# HEADER_1.net
KiCad netlist of a schematic drawn in Altium Designer
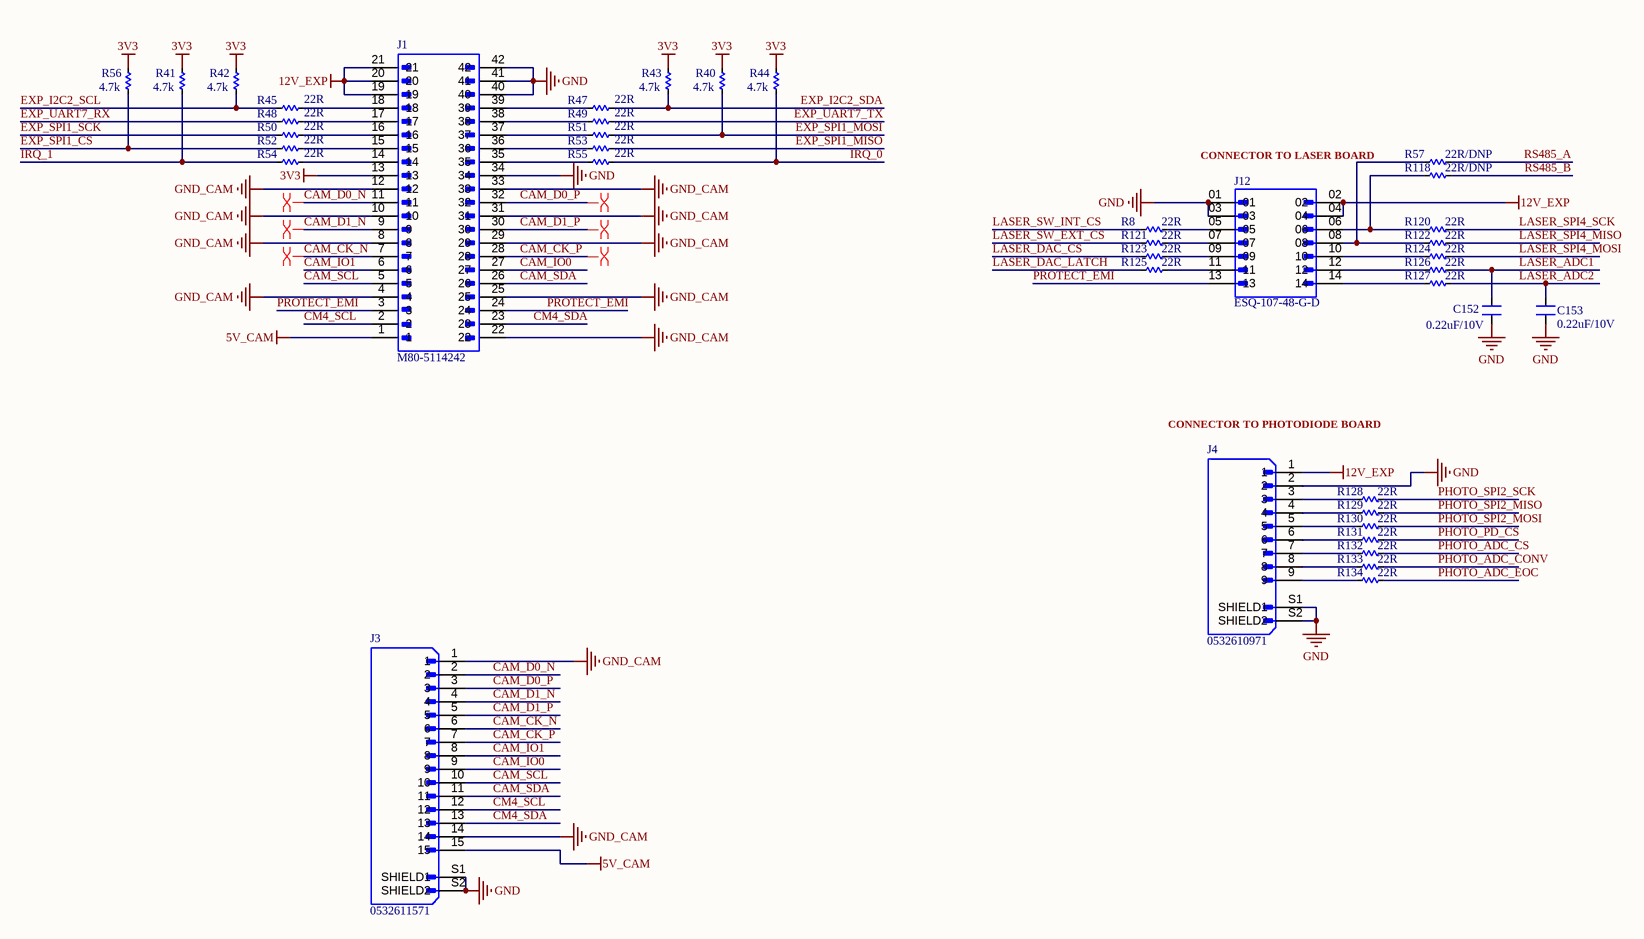
[diagram p0: HEADER_1.SchDoc]

(export (version "E")
  (design (tool "Eeschema 10.0.6"))
  (components
    (comp (ref "C152")
      (value "0.22uF/10V")
      (footprint "CAP_C_1608X80")
      (libsource (lib "EXP_HW_V3") (part "Capacitors"))
    )
    (comp (ref "C153")
      (value "0.22uF/10V")
      (footprint "CAP_C_1608X80")
      (libsource (lib "EXP_HW_V3") (part "Capacitors"))
    )
    (comp (ref "J1")
      (value "M80-5114242")
      (footprint "M80-5114242")
      (description "CONN HEADER VERT 42POS 2MM")
      (libsource (lib "EXP_HW_V2") (part "CONN_TH_42"))
    )
    (comp (ref "J3")
      (value "0532611571")
      (footprint "0532611571")
      (description "Conn Shrouded Header (4 Sides) HDR 15 POS 1.25mm Solder RA Side Entry SMD PicoBladeâ„¢ T/R")
      (fields (field (name "MP") "532611571") (field (name "MF") "Molex"))
      (libsource (lib "EXP_HW_V2") (part "CONN_SMD_15"))
    )
    (comp (ref "J4")
      (value "0532610971")
      (footprint "0532610971")
      (description "CONN HEADER SMD R/A 9POS 1.25MM")
      (libsource (lib "EXP_HW_V3") (part "CONN_SMD_09"))
    )
    (comp (ref "J12")
      (value "ESQ-107-48-G-D")
      (footprint "ESQ-107-37-G-D")
      (description "CONN SOCKET 14POS 0.1 GOLD PCB")
      (libsource (lib "EXP_HW_V2") (part "CONN_TH_14"))
    )
    (comp (ref "R8")
      (value "22R")
      (footprint "RES_C_1608X60")
      (description "SMD")
      (fields
        (field (name "MANUFACTURER") "Generic Components")
        (field (name "PUBLISHER") "Altium Hobart Technology Centre")
      )
      (libsource (lib "EXP_HW_V3") (part "Res SMD"))
    )
    (comp (ref "R40")
      (value "4.7k")
      (footprint "RES_C_1608X60")
      (description "SMD")
      (fields
        (field (name "MANUFACTURER") "Generic Components")
        (field (name "PUBLISHER") "Altium Hobart Technology Centre")
      )
      (libsource (lib "EXP_HW_V3") (part "Res SMD"))
    )
    (comp (ref "R41")
      (value "4.7k")
      (footprint "RES_C_1608X60")
      (description "SMD")
      (fields
        (field (name "MANUFACTURER") "Generic Components")
        (field (name "PUBLISHER") "Altium Hobart Technology Centre")
      )
      (libsource (lib "EXP_HW_V3") (part "Res SMD"))
    )
    (comp (ref "R42")
      (value "4.7k")
      (footprint "RES_C_1608X60")
      (description "SMD")
      (fields
        (field (name "MANUFACTURER") "Generic Components")
        (field (name "PUBLISHER") "Altium Hobart Technology Centre")
      )
      (libsource (lib "EXP_HW_V3") (part "Res SMD"))
    )
    (comp (ref "R43")
      (value "4.7k")
      (footprint "RES_C_1608X60")
      (description "SMD")
      (fields
        (field (name "MANUFACTURER") "Generic Components")
        (field (name "PUBLISHER") "Altium Hobart Technology Centre")
      )
      (libsource (lib "EXP_HW_V3") (part "Res SMD"))
    )
    (comp (ref "R44")
      (value "4.7k")
      (footprint "RES_C_1608X60")
      (description "SMD")
      (fields
        (field (name "MANUFACTURER") "Generic Components")
        (field (name "PUBLISHER") "Altium Hobart Technology Centre")
      )
      (libsource (lib "EXP_HW_V3") (part "Res SMD"))
    )
    (comp (ref "R45")
      (value "22R")
      (footprint "RES_C_1608X60")
      (description "SMD")
      (fields
        (field (name "MANUFACTURER") "Generic Components")
        (field (name "PUBLISHER") "Altium Hobart Technology Centre")
      )
      (libsource (lib "EXP_HW_V3") (part "Res SMD"))
    )
    (comp (ref "R47")
      (value "22R")
      (footprint "RES_C_1608X60")
      (description "SMD")
      (fields
        (field (name "MANUFACTURER") "Generic Components")
        (field (name "PUBLISHER") "Altium Hobart Technology Centre")
      )
      (libsource (lib "EXP_HW_V3") (part "Res SMD"))
    )
    (comp (ref "R48")
      (value "22R")
      (footprint "RES_C_1608X60")
      (description "SMD")
      (fields
        (field (name "MANUFACTURER") "Generic Components")
        (field (name "PUBLISHER") "Altium Hobart Technology Centre")
      )
      (libsource (lib "EXP_HW_V3") (part "Res SMD"))
    )
    (comp (ref "R49")
      (value "22R")
      (footprint "RES_C_1608X60")
      (description "SMD")
      (fields
        (field (name "MANUFACTURER") "Generic Components")
        (field (name "PUBLISHER") "Altium Hobart Technology Centre")
      )
      (libsource (lib "EXP_HW_V3") (part "Res SMD"))
    )
    (comp (ref "R50")
      (value "22R")
      (footprint "RES_C_1608X60")
      (description "SMD")
      (fields
        (field (name "MANUFACTURER") "Generic Components")
        (field (name "PUBLISHER") "Altium Hobart Technology Centre")
      )
      (libsource (lib "EXP_HW_V3") (part "Res SMD"))
    )
    (comp (ref "R51")
      (value "22R")
      (footprint "RES_C_1608X60")
      (description "SMD")
      (fields
        (field (name "MANUFACTURER") "Generic Components")
        (field (name "PUBLISHER") "Altium Hobart Technology Centre")
      )
      (libsource (lib "EXP_HW_V3") (part "Res SMD"))
    )
    (comp (ref "R52")
      (value "22R")
      (footprint "RES_C_1608X60")
      (description "SMD")
      (fields
        (field (name "MANUFACTURER") "Generic Components")
        (field (name "PUBLISHER") "Altium Hobart Technology Centre")
      )
      (libsource (lib "EXP_HW_V3") (part "Res SMD"))
    )
    (comp (ref "R53")
      (value "22R")
      (footprint "RES_C_1608X60")
      (description "SMD")
      (fields
        (field (name "MANUFACTURER") "Generic Components")
        (field (name "PUBLISHER") "Altium Hobart Technology Centre")
      )
      (libsource (lib "EXP_HW_V3") (part "Res SMD"))
    )
    (comp (ref "R54")
      (value "22R")
      (footprint "RES_C_1608X60")
      (description "SMD")
      (fields
        (field (name "MANUFACTURER") "Generic Components")
        (field (name "PUBLISHER") "Altium Hobart Technology Centre")
      )
      (libsource (lib "EXP_HW_V3") (part "Res SMD"))
    )
    (comp (ref "R55")
      (value "22R")
      (footprint "RES_C_1608X60")
      (description "SMD")
      (fields
        (field (name "MANUFACTURER") "Generic Components")
        (field (name "PUBLISHER") "Altium Hobart Technology Centre")
      )
      (libsource (lib "EXP_HW_V3") (part "Res SMD"))
    )
    (comp (ref "R56")
      (value "4.7k")
      (footprint "RES_C_1608X60")
      (description "SMD")
      (fields
        (field (name "MANUFACTURER") "Generic Components")
        (field (name "PUBLISHER") "Altium Hobart Technology Centre")
      )
      (libsource (lib "EXP_HW_V3") (part "Res SMD"))
    )
    (comp (ref "R57")
      (value "22R/DNP")
      (footprint "RES_C_1608X60")
      (description "SMD")
      (fields
        (field (name "MANUFACTURER") "Generic Components")
        (field (name "PUBLISHER") "Altium Hobart Technology Centre")
      )
      (libsource (lib "EXP_HW_V3") (part "Res SMD"))
    )
    (comp (ref "R118")
      (value "22R/DNP")
      (footprint "RES_C_1608X60")
      (description "SMD")
      (fields
        (field (name "MANUFACTURER") "Generic Components")
        (field (name "PUBLISHER") "Altium Hobart Technology Centre")
      )
      (libsource (lib "EXP_HW_V3") (part "Res SMD"))
    )
    (comp (ref "R120")
      (value "22R")
      (footprint "RES_C_1608X60")
      (description "SMD")
      (fields
        (field (name "MANUFACTURER") "Generic Components")
        (field (name "PUBLISHER") "Altium Hobart Technology Centre")
      )
      (libsource (lib "EXP_HW_V3") (part "Res SMD"))
    )
    (comp (ref "R121")
      (value "22R")
      (footprint "RES_C_1608X60")
      (description "SMD")
      (fields
        (field (name "MANUFACTURER") "Generic Components")
        (field (name "PUBLISHER") "Altium Hobart Technology Centre")
      )
      (libsource (lib "EXP_HW_V3") (part "Res SMD"))
    )
    (comp (ref "R122")
      (value "22R")
      (footprint "RES_C_1608X60")
      (description "SMD")
      (fields
        (field (name "MANUFACTURER") "Generic Components")
        (field (name "PUBLISHER") "Altium Hobart Technology Centre")
      )
      (libsource (lib "EXP_HW_V3") (part "Res SMD"))
    )
    (comp (ref "R123")
      (value "22R")
      (footprint "RES_C_1608X60")
      (description "SMD")
      (fields
        (field (name "MANUFACTURER") "Generic Components")
        (field (name "PUBLISHER") "Altium Hobart Technology Centre")
      )
      (libsource (lib "EXP_HW_V3") (part "Res SMD"))
    )
    (comp (ref "R124")
      (value "22R")
      (footprint "RES_C_1608X60")
      (description "SMD")
      (fields
        (field (name "MANUFACTURER") "Generic Components")
        (field (name "PUBLISHER") "Altium Hobart Technology Centre")
      )
      (libsource (lib "EXP_HW_V3") (part "Res SMD"))
    )
    (comp (ref "R125")
      (value "22R")
      (footprint "RES_C_1608X60")
      (description "SMD")
      (fields
        (field (name "MANUFACTURER") "Generic Components")
        (field (name "PUBLISHER") "Altium Hobart Technology Centre")
      )
      (libsource (lib "EXP_HW_V3") (part "Res SMD"))
    )
    (comp (ref "R126")
      (value "22R")
      (footprint "RES_C_1608X60")
      (description "SMD")
      (fields
        (field (name "MANUFACTURER") "Generic Components")
        (field (name "PUBLISHER") "Altium Hobart Technology Centre")
      )
      (libsource (lib "EXP_HW_V3") (part "Res SMD"))
    )
    (comp (ref "R127")
      (value "22R")
      (footprint "RES_C_1608X60")
      (description "SMD")
      (fields
        (field (name "MANUFACTURER") "Generic Components")
        (field (name "PUBLISHER") "Altium Hobart Technology Centre")
      )
      (libsource (lib "EXP_HW_V3") (part "Res SMD"))
    )
    (comp (ref "R128")
      (value "22R")
      (footprint "RES_C_1608X60")
      (description "SMD")
      (fields
        (field (name "MANUFACTURER") "Generic Components")
        (field (name "PUBLISHER") "Altium Hobart Technology Centre")
      )
      (libsource (lib "EXP_HW_V3") (part "Res SMD"))
    )
    (comp (ref "R129")
      (value "22R")
      (footprint "RES_C_1608X60")
      (description "SMD")
      (fields
        (field (name "MANUFACTURER") "Generic Components")
        (field (name "PUBLISHER") "Altium Hobart Technology Centre")
      )
      (libsource (lib "EXP_HW_V3") (part "Res SMD"))
    )
    (comp (ref "R130")
      (value "22R")
      (footprint "RES_C_1608X60")
      (description "SMD")
      (fields
        (field (name "MANUFACTURER") "Generic Components")
        (field (name "PUBLISHER") "Altium Hobart Technology Centre")
      )
      (libsource (lib "EXP_HW_V3") (part "Res SMD"))
    )
    (comp (ref "R131")
      (value "22R")
      (footprint "RES_C_1608X60")
      (description "SMD")
      (fields
        (field (name "MANUFACTURER") "Generic Components")
        (field (name "PUBLISHER") "Altium Hobart Technology Centre")
      )
      (libsource (lib "EXP_HW_V3") (part "Res SMD"))
    )
    (comp (ref "R132")
      (value "22R")
      (footprint "RES_C_1608X60")
      (description "SMD")
      (fields
        (field (name "MANUFACTURER") "Generic Components")
        (field (name "PUBLISHER") "Altium Hobart Technology Centre")
      )
      (libsource (lib "EXP_HW_V3") (part "Res SMD"))
    )
    (comp (ref "R133")
      (value "22R")
      (footprint "RES_C_1608X60")
      (description "SMD")
      (fields
        (field (name "MANUFACTURER") "Generic Components")
        (field (name "PUBLISHER") "Altium Hobart Technology Centre")
      )
      (libsource (lib "EXP_HW_V3") (part "Res SMD"))
    )
    (comp (ref "R134")
      (value "22R")
      (footprint "RES_C_1608X60")
      (description "SMD")
      (fields
        (field (name "MANUFACTURER") "Generic Components")
        (field (name "PUBLISHER") "Altium Hobart Technology Centre")
      )
      (libsource (lib "EXP_HW_V3") (part "Res SMD"))
    )
  )
  (nets
    (net (code "1") (name "/CAM_CK_N") (class "Default")
      (node (ref "J1") (pin "7") (pinfunction "7_7") (pintype "passive"))
      (node (ref "J3") (pin "6") (pinfunction "6_6") (pintype "passive"))
    )
    (net (code "2") (name "/CAM_CK_P") (class "Default")
      (node (ref "J1") (pin "28") (pinfunction "28_28") (pintype "passive"))
      (node (ref "J3") (pin "7") (pinfunction "7_7") (pintype "passive"))
    )
    (net (code "3") (name "/CAM_D0_N") (class "Default")
      (node (ref "J1") (pin "11") (pinfunction "11_11") (pintype "passive"))
      (node (ref "J3") (pin "2") (pinfunction "2_2") (pintype "passive"))
    )
    (net (code "4") (name "/CAM_D0_P") (class "Default")
      (node (ref "J1") (pin "32") (pinfunction "32_32") (pintype "passive"))
      (node (ref "J3") (pin "3") (pinfunction "3_3") (pintype "passive"))
    )
    (net (code "5") (name "/CAM_D1_N") (class "Default")
      (node (ref "J1") (pin "9") (pinfunction "9_9") (pintype "passive"))
      (node (ref "J3") (pin "4") (pinfunction "4_4") (pintype "passive"))
    )
    (net (code "6") (name "/CAM_D1_P") (class "Default")
      (node (ref "J1") (pin "30") (pinfunction "30_30") (pintype "passive"))
      (node (ref "J3") (pin "5") (pinfunction "5_5") (pintype "passive"))
    )
    (net (code "7") (name "/CAM_IO0") (class "Default")
      (node (ref "J1") (pin "27") (pinfunction "27_27") (pintype "passive"))
      (node (ref "J3") (pin "9") (pinfunction "9_9") (pintype "passive"))
    )
    (net (code "8") (name "/CAM_IO1") (class "Default")
      (node (ref "J1") (pin "6") (pinfunction "6_6") (pintype "passive"))
      (node (ref "J3") (pin "8") (pinfunction "8_8") (pintype "passive"))
    )
    (net (code "9") (name "/CAM_SCL") (class "Default")
      (node (ref "J1") (pin "5") (pinfunction "5_5") (pintype "passive"))
      (node (ref "J3") (pin "10") (pinfunction "10_10") (pintype "passive"))
    )
    (net (code "10") (name "/CAM_SDA") (class "Default")
      (node (ref "J1") (pin "26") (pinfunction "26_26") (pintype "passive"))
      (node (ref "J3") (pin "11") (pinfunction "11_11") (pintype "passive"))
    )
    (net (code "11") (name "/CM4_SCL") (class "Default")
      (node (ref "J1") (pin "2") (pinfunction "2_2") (pintype "passive"))
      (node (ref "J3") (pin "12") (pinfunction "12_12") (pintype "passive"))
    )
    (net (code "12") (name "/CM4_SDA") (class "Default")
      (node (ref "J1") (pin "23") (pinfunction "23_23") (pintype "passive"))
      (node (ref "J3") (pin "13") (pinfunction "13_13") (pintype "passive"))
    )
    (net (code "13") (name "/EXP_I2C2_SCL") (class "Default")
      (node (ref "R42") (pin "2") (pinfunction "2_2") (pintype "passive"))
      (node (ref "R45") (pin "1") (pinfunction "1_1") (pintype "passive"))
    )
    (net (code "14") (name "/EXP_I2C2_SDA") (class "Default")
      (node (ref "R43") (pin "2") (pinfunction "2_2") (pintype "passive"))
      (node (ref "R47") (pin "2") (pinfunction "2_2") (pintype "passive"))
    )
    (net (code "15") (name "/EXP_SPI1_CS") (class "Default")
      (node (ref "R52") (pin "1") (pinfunction "1_1") (pintype "passive"))
      (node (ref "R56") (pin "2") (pinfunction "2_2") (pintype "passive"))
    )
    (net (code "16") (name "/EXP_SPI1_MISO") (class "Default")
      (node (ref "R53") (pin "2") (pinfunction "2_2") (pintype "passive"))
    )
    (net (code "17") (name "/EXP_SPI1_MOSI") (class "Default")
      (node (ref "R40") (pin "2") (pinfunction "2_2") (pintype "passive"))
      (node (ref "R51") (pin "2") (pinfunction "2_2") (pintype "passive"))
    )
    (net (code "18") (name "/EXP_SPI1_SCK") (class "Default")
      (node (ref "R50") (pin "1") (pinfunction "1_1") (pintype "passive"))
    )
    (net (code "19") (name "/EXP_UART7_RX") (class "Default")
      (node (ref "R48") (pin "1") (pinfunction "1_1") (pintype "passive"))
    )
    (net (code "20") (name "/EXP_UART7_TX") (class "Default")
      (node (ref "R49") (pin "2") (pinfunction "2_2") (pintype "passive"))
    )
    (net (code "21") (name "/IRQ_0") (class "Default")
      (node (ref "R44") (pin "2") (pinfunction "2_2") (pintype "passive"))
      (node (ref "R55") (pin "2") (pinfunction "2_2") (pintype "passive"))
    )
    (net (code "22") (name "/IRQ_1") (class "Default")
      (node (ref "R41") (pin "2") (pinfunction "2_2") (pintype "passive"))
      (node (ref "R54") (pin "1") (pinfunction "1_1") (pintype "passive"))
    )
    (net (code "23") (name "/LASER_ADC1") (class "Default")
      (node (ref "C152") (pin "2") (pinfunction "2_2") (pintype "passive"))
      (node (ref "R126") (pin "2") (pinfunction "2_2") (pintype "passive"))
    )
    (net (code "24") (name "/LASER_ADC2") (class "Default")
      (node (ref "C153") (pin "2") (pinfunction "2_2") (pintype "passive"))
      (node (ref "R127") (pin "2") (pinfunction "2_2") (pintype "passive"))
    )
    (net (code "25") (name "/LASER_DAC_CS") (class "Default")
      (node (ref "R123") (pin "1") (pinfunction "1_1") (pintype "passive"))
    )
    (net (code "26") (name "/LASER_DAC_LATCH") (class "Default")
      (node (ref "R125") (pin "1") (pinfunction "1_1") (pintype "passive"))
    )
    (net (code "27") (name "/LASER_SPI4_MISO") (class "Default")
      (node (ref "R122") (pin "2") (pinfunction "2_2") (pintype "passive"))
    )
    (net (code "28") (name "/LASER_SPI4_MOSI") (class "Default")
      (node (ref "R124") (pin "2") (pinfunction "2_2") (pintype "passive"))
    )
    (net (code "29") (name "/LASER_SPI4_SCK") (class "Default")
      (node (ref "R120") (pin "2") (pinfunction "2_2") (pintype "passive"))
    )
    (net (code "30") (name "/LASER_SW_EXT_CS") (class "Default")
      (node (ref "R121") (pin "1") (pinfunction "1_1") (pintype "passive"))
    )
    (net (code "31") (name "/LASER_SW_INT_CS") (class "Default")
      (node (ref "R8") (pin "1") (pinfunction "1_1") (pintype "passive"))
    )
    (net (code "32") (name "/PHOTO_ADC_CONV") (class "Default")
      (node (ref "R133") (pin "2") (pinfunction "2_2") (pintype "passive"))
    )
    (net (code "33") (name "/PHOTO_ADC_CS") (class "Default")
      (node (ref "R132") (pin "2") (pinfunction "2_2") (pintype "passive"))
    )
    (net (code "34") (name "/PHOTO_ADC_EOC") (class "Default")
      (node (ref "R134") (pin "2") (pinfunction "2_2") (pintype "passive"))
    )
    (net (code "35") (name "/PHOTO_PD_CS") (class "Default")
      (node (ref "R131") (pin "2") (pinfunction "2_2") (pintype "passive"))
    )
    (net (code "36") (name "/PHOTO_SPI2_MISO") (class "Default")
      (node (ref "R129") (pin "2") (pinfunction "2_2") (pintype "passive"))
    )
    (net (code "37") (name "/PHOTO_SPI2_MOSI") (class "Default")
      (node (ref "R130") (pin "2") (pinfunction "2_2") (pintype "passive"))
    )
    (net (code "38") (name "/PHOTO_SPI2_SCK") (class "Default")
      (node (ref "R128") (pin "2") (pinfunction "2_2") (pintype "passive"))
    )
    (net (code "39") (name "/PROTECT_EMI") (class "Default")
      (node (ref "J1") (pin "24") (pinfunction "24_24") (pintype "passive"))
      (node (ref "J1") (pin "3") (pinfunction "3_3") (pintype "passive"))
      (node (ref "J12") (pin "13") (pinfunction "13_13") (pintype "passive"))
    )
    (net (code "40") (name "/RS485_A") (class "Default")
      (node (ref "R57") (pin "2") (pinfunction "2_2") (pintype "passive"))
    )
    (net (code "41") (name "/RS485_B") (class "Default")
      (node (ref "R118") (pin "2") (pinfunction "2_2") (pintype "passive"))
    )
    (net (code "42") (name "3V3") (class "Default")
      (node (ref "J1") (pin "13") (pinfunction "13_13") (pintype "passive"))
      (node (ref "R40") (pin "1") (pinfunction "1_1") (pintype "passive"))
      (node (ref "R41") (pin "1") (pinfunction "1_1") (pintype "passive"))
      (node (ref "R42") (pin "1") (pinfunction "1_1") (pintype "passive"))
      (node (ref "R43") (pin "1") (pinfunction "1_1") (pintype "passive"))
      (node (ref "R44") (pin "1") (pinfunction "1_1") (pintype "passive"))
      (node (ref "R56") (pin "1") (pinfunction "1_1") (pintype "passive"))
    )
    (net (code "43") (name "5V_CAM") (class "Default")
      (node (ref "J1") (pin "1") (pinfunction "1_1") (pintype "passive"))
      (node (ref "J3") (pin "15") (pinfunction "15_15") (pintype "passive"))
    )
    (net (code "44") (name "12V_EXP") (class "Default")
      (node (ref "J1") (pin "19") (pinfunction "19_19") (pintype "passive"))
      (node (ref "J1") (pin "20") (pinfunction "20_20") (pintype "passive"))
      (node (ref "J1") (pin "21") (pinfunction "21_21") (pintype "passive"))
      (node (ref "J12") (pin "02") (pinfunction "02_02") (pintype "passive"))
      (node (ref "J12") (pin "04") (pinfunction "04_04") (pintype "passive"))
      (node (ref "J4") (pin "1") (pinfunction "1_1") (pintype "passive"))
    )
    (net (code "45") (name "GND") (class "Default")
      (node (ref "C152") (pin "1") (pinfunction "1_1") (pintype "passive"))
      (node (ref "C153") (pin "1") (pinfunction "1_1") (pintype "passive"))
      (node (ref "J1") (pin "34") (pinfunction "34_34") (pintype "passive"))
      (node (ref "J1") (pin "40") (pinfunction "40_40") (pintype "passive"))
      (node (ref "J1") (pin "41") (pinfunction "41_41") (pintype "passive"))
      (node (ref "J1") (pin "42") (pinfunction "42_42") (pintype "passive"))
      (node (ref "J12") (pin "01") (pinfunction "01_01") (pintype "passive"))
      (node (ref "J12") (pin "03") (pinfunction "03_03") (pintype "passive"))
      (node (ref "J3") (pin "S1") (pinfunction "SHIELD1_S1") (pintype "passive"))
      (node (ref "J3") (pin "S2") (pinfunction "SHIELD2_S2") (pintype "passive"))
      (node (ref "J4") (pin "2") (pinfunction "2_2") (pintype "passive"))
      (node (ref "J4") (pin "S1") (pinfunction "SHIELD1_S1") (pintype "passive"))
      (node (ref "J4") (pin "S2") (pinfunction "SHIELD2_S2") (pintype "passive"))
    )
    (net (code "46") (name "GND_CAM") (class "Default")
      (node (ref "J1") (pin "10") (pinfunction "10_10") (pintype "passive"))
      (node (ref "J1") (pin "12") (pinfunction "12_12") (pintype "passive"))
      (node (ref "J1") (pin "22") (pinfunction "22_22") (pintype "passive"))
      (node (ref "J1") (pin "25") (pinfunction "25_25") (pintype "passive"))
      (node (ref "J1") (pin "29") (pinfunction "29_29") (pintype "passive"))
      (node (ref "J1") (pin "31") (pinfunction "31_31") (pintype "passive"))
      (node (ref "J1") (pin "33") (pinfunction "33_33") (pintype "passive"))
      (node (ref "J1") (pin "4") (pinfunction "4_4") (pintype "passive"))
      (node (ref "J1") (pin "8") (pinfunction "8_8") (pintype "passive"))
      (node (ref "J3") (pin "1") (pinfunction "1_1") (pintype "passive"))
      (node (ref "J3") (pin "14") (pinfunction "14_14") (pintype "passive"))
    )
    (net (code "47") (name "Net-(J1-Pad14)") (class "Default")
      (node (ref "J1") (pin "14") (pinfunction "14_14") (pintype "passive"))
      (node (ref "R54") (pin "2") (pinfunction "2_2") (pintype "passive"))
    )
    (net (code "48") (name "Net-(J1-Pad15)") (class "Default")
      (node (ref "J1") (pin "15") (pinfunction "15_15") (pintype "passive"))
      (node (ref "R52") (pin "2") (pinfunction "2_2") (pintype "passive"))
    )
    (net (code "49") (name "Net-(J1-Pad16)") (class "Default")
      (node (ref "J1") (pin "16") (pinfunction "16_16") (pintype "passive"))
      (node (ref "R50") (pin "2") (pinfunction "2_2") (pintype "passive"))
    )
    (net (code "50") (name "Net-(J1-Pad17)") (class "Default")
      (node (ref "J1") (pin "17") (pinfunction "17_17") (pintype "passive"))
      (node (ref "R48") (pin "2") (pinfunction "2_2") (pintype "passive"))
    )
    (net (code "51") (name "Net-(J1-Pad18)") (class "Default")
      (node (ref "J1") (pin "18") (pinfunction "18_18") (pintype "passive"))
      (node (ref "R45") (pin "2") (pinfunction "2_2") (pintype "passive"))
    )
    (net (code "52") (name "Net-(J1-Pad35)") (class "Default")
      (node (ref "J1") (pin "35") (pinfunction "35_35") (pintype "passive"))
      (node (ref "R55") (pin "1") (pinfunction "1_1") (pintype "passive"))
    )
    (net (code "53") (name "Net-(J1-Pad36)") (class "Default")
      (node (ref "J1") (pin "36") (pinfunction "36_36") (pintype "passive"))
      (node (ref "R53") (pin "1") (pinfunction "1_1") (pintype "passive"))
    )
    (net (code "54") (name "Net-(J1-Pad37)") (class "Default")
      (node (ref "J1") (pin "37") (pinfunction "37_37") (pintype "passive"))
      (node (ref "R51") (pin "1") (pinfunction "1_1") (pintype "passive"))
    )
    (net (code "55") (name "Net-(J1-Pad38)") (class "Default")
      (node (ref "J1") (pin "38") (pinfunction "38_38") (pintype "passive"))
      (node (ref "R49") (pin "1") (pinfunction "1_1") (pintype "passive"))
    )
    (net (code "56") (name "Net-(J1-Pad39)") (class "Default")
      (node (ref "J1") (pin "39") (pinfunction "39_39") (pintype "passive"))
      (node (ref "R47") (pin "1") (pinfunction "1_1") (pintype "passive"))
    )
    (net (code "57") (name "Net-(J4-Pad3)") (class "Default")
      (node (ref "J4") (pin "3") (pinfunction "3_3") (pintype "passive"))
      (node (ref "R128") (pin "1") (pinfunction "1_1") (pintype "passive"))
    )
    (net (code "58") (name "Net-(J4-Pad4)") (class "Default")
      (node (ref "J4") (pin "4") (pinfunction "4_4") (pintype "passive"))
      (node (ref "R129") (pin "1") (pinfunction "1_1") (pintype "passive"))
    )
    (net (code "59") (name "Net-(J4-Pad5)") (class "Default")
      (node (ref "J4") (pin "5") (pinfunction "5_5") (pintype "passive"))
      (node (ref "R130") (pin "1") (pinfunction "1_1") (pintype "passive"))
    )
    (net (code "60") (name "Net-(J4-Pad6)") (class "Default")
      (node (ref "J4") (pin "6") (pinfunction "6_6") (pintype "passive"))
      (node (ref "R131") (pin "1") (pinfunction "1_1") (pintype "passive"))
    )
    (net (code "61") (name "Net-(J4-Pad7)") (class "Default")
      (node (ref "J4") (pin "7") (pinfunction "7_7") (pintype "passive"))
      (node (ref "R132") (pin "1") (pinfunction "1_1") (pintype "passive"))
    )
    (net (code "62") (name "Net-(J4-Pad8)") (class "Default")
      (node (ref "J4") (pin "8") (pinfunction "8_8") (pintype "passive"))
      (node (ref "R133") (pin "1") (pinfunction "1_1") (pintype "passive"))
    )
    (net (code "63") (name "Net-(J4-Pad9)") (class "Default")
      (node (ref "J4") (pin "9") (pinfunction "9_9") (pintype "passive"))
      (node (ref "R134") (pin "1") (pinfunction "1_1") (pintype "passive"))
    )
    (net (code "64") (name "Net-(J12-Pad05)") (class "Default")
      (node (ref "J12") (pin "05") (pinfunction "05_05") (pintype "passive"))
      (node (ref "R8") (pin "2") (pinfunction "2_2") (pintype "passive"))
    )
    (net (code "65") (name "Net-(J12-Pad06)") (class "Default")
      (node (ref "J12") (pin "06") (pinfunction "06_06") (pintype "passive"))
      (node (ref "R118") (pin "1") (pinfunction "1_1") (pintype "passive"))
      (node (ref "R120") (pin "1") (pinfunction "1_1") (pintype "passive"))
    )
    (net (code "66") (name "Net-(J12-Pad07)") (class "Default")
      (node (ref "J12") (pin "07") (pinfunction "07_07") (pintype "passive"))
      (node (ref "R121") (pin "2") (pinfunction "2_2") (pintype "passive"))
    )
    (net (code "67") (name "Net-(J12-Pad08)") (class "Default")
      (node (ref "J12") (pin "08") (pinfunction "08_08") (pintype "passive"))
      (node (ref "R122") (pin "1") (pinfunction "1_1") (pintype "passive"))
      (node (ref "R57") (pin "1") (pinfunction "1_1") (pintype "passive"))
    )
    (net (code "68") (name "Net-(J12-Pad09)") (class "Default")
      (node (ref "J12") (pin "09") (pinfunction "09_09") (pintype "passive"))
      (node (ref "R123") (pin "2") (pinfunction "2_2") (pintype "passive"))
    )
    (net (code "69") (name "Net-(J12-Pad10)") (class "Default")
      (node (ref "J12") (pin "10") (pinfunction "10_10") (pintype "passive"))
      (node (ref "R124") (pin "1") (pinfunction "1_1") (pintype "passive"))
    )
    (net (code "70") (name "Net-(J12-Pad11)") (class "Default")
      (node (ref "J12") (pin "11") (pinfunction "11_11") (pintype "passive"))
      (node (ref "R125") (pin "2") (pinfunction "2_2") (pintype "passive"))
    )
    (net (code "71") (name "Net-(J12-Pad12)") (class "Default")
      (node (ref "J12") (pin "12") (pinfunction "12_12") (pintype "passive"))
      (node (ref "R126") (pin "1") (pinfunction "1_1") (pintype "passive"))
    )
    (net (code "72") (name "Net-(J12-Pad14)") (class "Default")
      (node (ref "J12") (pin "14") (pinfunction "14_14") (pintype "passive"))
      (node (ref "R127") (pin "1") (pinfunction "1_1") (pintype "passive"))
    )
  )
)
